# STM32_MCU.net
KiCad netlist of a schematic drawn in Altium Designer
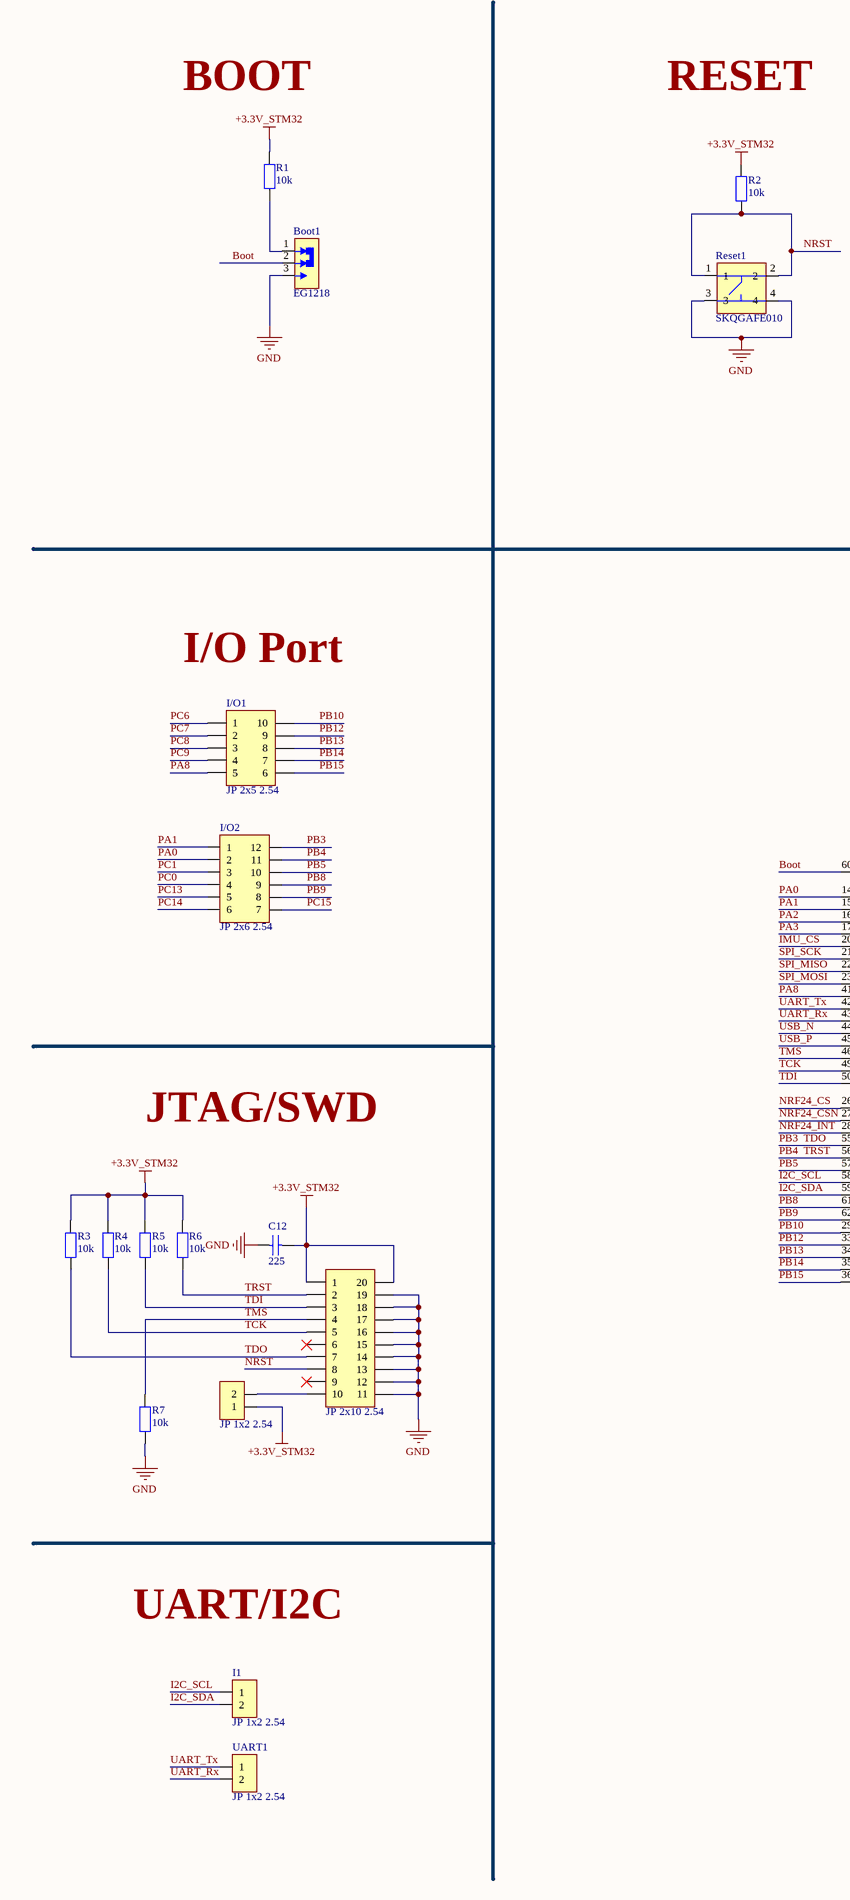
[diagram p0: STM32_MCU.SchDoc, left]
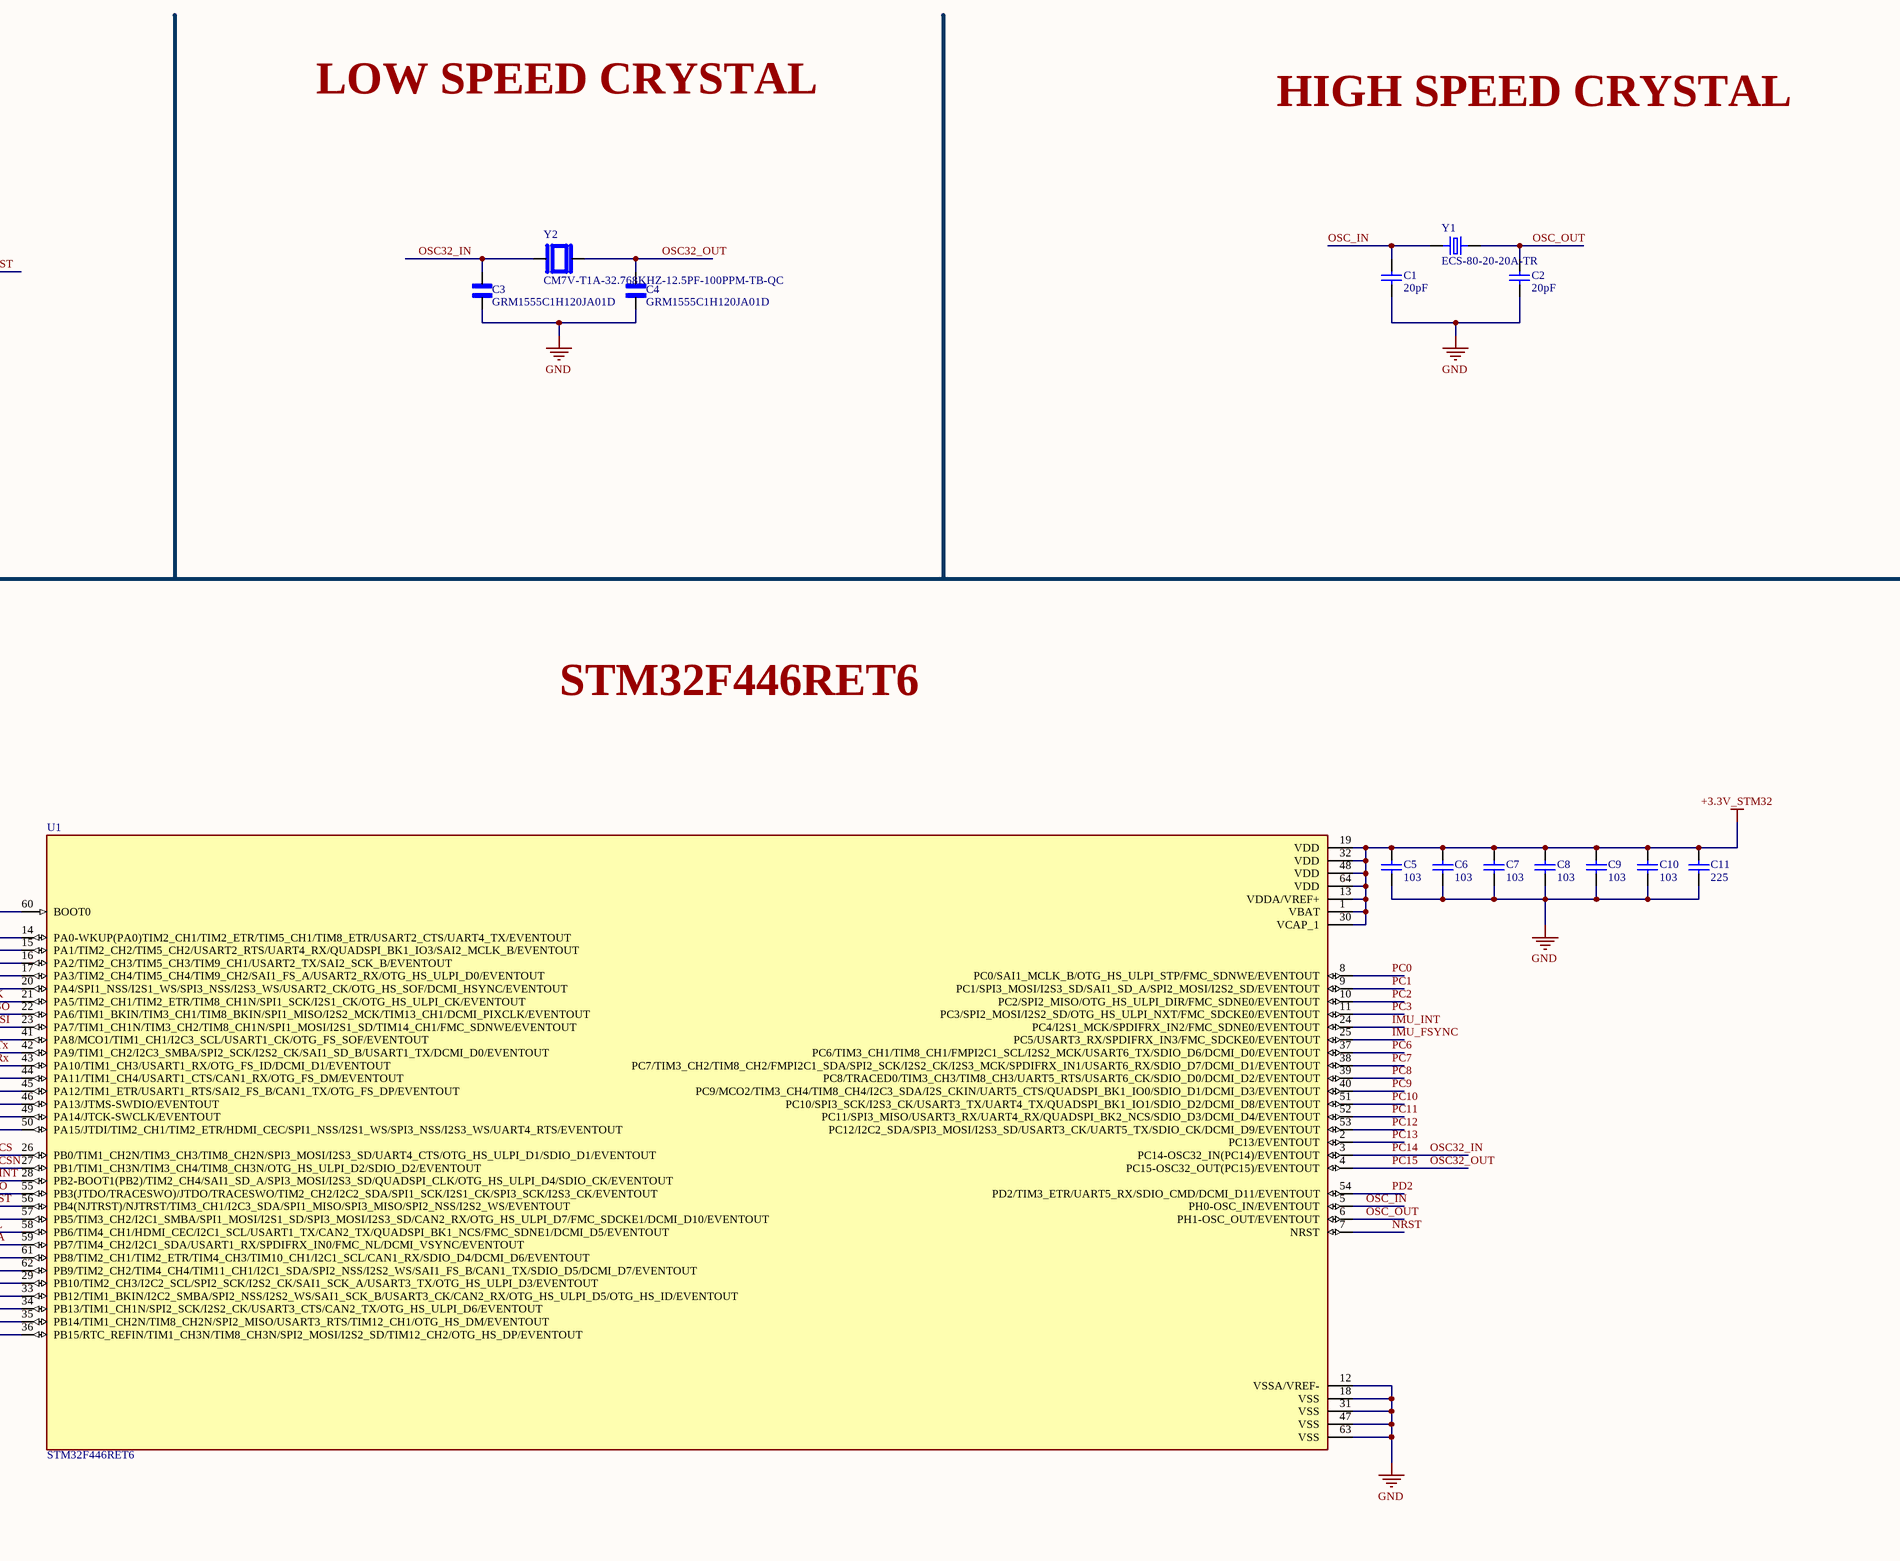
[diagram p1: STM32_MCU.SchDoc, right]

(export (version "E")
  (design (tool "Eeschema 10.0.6"))
  (components
    (comp (ref "Boot1")
      (value "EG1218")
      (footprint "SW_EG1218")
      (description "Slide Switch, EG Series, SPDT, Non-Shorting, ON-ON, 200mA DC, 30VDC, PC Pin ¦ E-Switch EG1218")
      (fields (field (name "MF") "E-Switch"))
      (libsource (lib "EG1218") (part "EG1218"))
    )
    (comp (ref "C1")
      (value "20pF")
      (footprint "tu 0805")
      (description "Dán")
      (libsource (lib "Altium_Lib_by_KhueNguyenCreator") (part "Tu 0805 20pF 50V 10%"))
    )
    (comp (ref "C2")
      (value "20pF")
      (footprint "tu 0805")
      (description "Dán")
      (libsource (lib "Altium_Lib_by_KhueNguyenCreator") (part "Tu 0805 20pF 50V 10%"))
    )
    (comp (ref "C3")
      (value "GRM1555C1H120JA01D")
      (footprint "GRM1555C1H120JA01D:CAPC1005X55N")
      (description "0402 12 pF 50 V Â±5% Tolerance C0G SMT Multilayer Ceramic Capacitor")
      (fields (field (name "MF") "{'manufacturer': u'Murata'}"))
      (libsource (lib "*") (part "GRM1555C1H120JA01D"))
    )
    (comp (ref "C4")
      (value "GRM1555C1H120JA01D")
      (footprint "GRM1555C1H120JA01D:CAPC1005X55N")
      (description "0402 12 pF 50 V Â±5% Tolerance C0G SMT Multilayer Ceramic Capacitor")
      (fields (field (name "MF") "{'manufacturer': u'Murata'}"))
      (libsource (lib "*") (part "GRM1555C1H120JA01D"))
    )
    (comp (ref "C5")
      (value "103")
      (footprint "tu 0603")
      (description "Dán")
      (libsource (lib "Altium_Lib_by_KhueNguyenCreator") (part "Tu 0603 103 50V 10%"))
    )
    (comp (ref "C6")
      (value "103")
      (footprint "tu 0603")
      (description "Dán")
      (libsource (lib "Altium_Lib_by_KhueNguyenCreator") (part "Tu 0603 103 50V 10%"))
    )
    (comp (ref "C7")
      (value "103")
      (footprint "tu 0603")
      (description "Dán")
      (libsource (lib "Altium_Lib_by_KhueNguyenCreator") (part "Tu 0603 103 50V 10%"))
    )
    (comp (ref "C8")
      (value "103")
      (footprint "tu 0603")
      (description "Dán")
      (libsource (lib "Altium_Lib_by_KhueNguyenCreator") (part "Tu 0603 103 50V 10%"))
    )
    (comp (ref "C9")
      (value "103")
      (footprint "tu 0603")
      (description "Dán")
      (libsource (lib "Altium_Lib_by_KhueNguyenCreator") (part "Tu 0603 103 50V 10%"))
    )
    (comp (ref "C10")
      (value "103")
      (footprint "tu 0603")
      (description "Dán")
      (libsource (lib "Altium_Lib_by_KhueNguyenCreator") (part "Tu 0603 103 50V 10%"))
    )
    (comp (ref "C11")
      (value "225")
      (footprint "tu 0805")
      (description "Dán")
      (libsource (lib "Altium_Lib_by_KhueNguyenCreator") (part "Tu 0805 225 25V 10%"))
    )
    (comp (ref "C12")
      (value "225")
      (footprint "tu 0805")
      (description "Dán")
      (libsource (lib "Altium_Lib_by_KhueNguyenCreator") (part "Tu 0805 225 25V 10%"))
    )
    (comp (ref "I/O1")
      (value "JP 2x5 2.54")
      (footprint "JP 2x5 DT")
      (description "Cắm")
      (libsource (lib "Altium_Lib_by_KhueNguyenCreator") (part "JP 2x5 2.54 Duc Thang"))
    )
    (comp (ref "I/O2")
      (value "JP 2x6 2.54")
      (footprint "JP 2x6 DT")
      (description "Cắm")
      (libsource (lib "Altium_Lib_by_KhueNguyenCreator") (part "JP 2x6 2.54 Duc Thang"))
    )
    (comp (ref "I1")
      (value "JP 1x2 2.54")
      (footprint "JP 1x2 DT")
      (description "Cắm")
      (libsource (lib "Altium_Lib_by_KhueNguyenCreator") (part "JP 1x2 2.54 Duc Thang"))
    )
    (comp (ref "JP1")
      (value "JP 1x2 2.54")
      (footprint "JP 1x2 DT")
      (description "Cắm")
      (libsource (lib "") (part "JP 1x2 2.54 Duc Thang_1"))
    )
    (comp (ref "R1")
      (value "10k")
      (footprint "tro smd 0603")
      (description "Dán")
      (libsource (lib "Altium_Lib_by_KhueNguyenCreator") (part "Tro 0603 1% 10k"))
    )
    (comp (ref "R2")
      (value "10k")
      (footprint "tro smd 0603")
      (description "Dán")
      (libsource (lib "Altium_Lib_by_KhueNguyenCreator") (part "Tro 0603 1% 10k"))
    )
    (comp (ref "R3")
      (value "10k")
      (footprint "tro smd 0603")
      (description "Dán")
      (libsource (lib "Altium_Lib_by_KhueNguyenCreator") (part "Tro 0603 1% 10k"))
    )
    (comp (ref "R4")
      (value "10k")
      (footprint "tro smd 0603")
      (description "Dán")
      (libsource (lib "Altium_Lib_by_KhueNguyenCreator") (part "Tro 0603 1% 10k"))
    )
    (comp (ref "R5")
      (value "10k")
      (footprint "tro smd 0603")
      (description "Dán")
      (libsource (lib "Altium_Lib_by_KhueNguyenCreator") (part "Tro 0603 1% 10k"))
    )
    (comp (ref "R6")
      (value "10k")
      (footprint "tro smd 0603")
      (description "Dán")
      (libsource (lib "Altium_Lib_by_KhueNguyenCreator") (part "Tro 0603 1% 10k"))
    )
    (comp (ref "R7")
      (value "10k")
      (footprint "tro smd 0603")
      (description "Dán")
      (libsource (lib "Altium_Lib_by_KhueNguyenCreator") (part "Tro 0603 1% 10k"))
    )
    (comp (ref "Reset1")
      (value "SKQGAFE010")
      (footprint "SW_SKQGAFE010")
      (description "Switch Tactile N.O. SPST Button Gull Wing 0.05A 12VDC 0.98N SMD T/R")
      (fields (field (name "MF") "{'manufacturer': u'ALPS'}"))
      (libsource (lib "SnapEDA_Library") (part "SKQGAFE010"))
    )
    (comp (ref "SWD/JTAG1")
      (value "JP 2x10 2.54")
      (footprint "JP 2x10 DT")
      (description "Cắm")
      (libsource (lib "Altium_Lib_by_KhueNguyenCreator") (part "JP 2x10 2.54 Duc Thang"))
    )
    (comp (ref "U1")
      (value "STM32F446RET6")
      (footprint "QFP50P1200X1200X160-64N")
      (description "MCU 32-Bit STM32 ARM Cortex M4 RISC 512KB Flash 2.5V/3.3V 64-Pin LQFP Tray")
      (fields (field (name "MF") "{'manufacturer': u'STMicroelectronics'}"))
      (libsource (lib "SnapEDA_Library") (part "STM32F446RET6"))
    )
    (comp (ref "UART1")
      (value "JP 1x2 2.54")
      (footprint "JP 1x2 DT")
      (description "Cắm")
      (libsource (lib "Altium_Lib_by_KhueNguyenCreator") (part "JP 1x2 2.54 Duc Thang"))
    )
    (comp (ref "Y1")
      (value "ECS-80-20-20A-TR")
      (footprint "ECS-80-20-20A-TR:XTAL_ECS-80-20-20A-TR")
      (description "SMD CRYSTAL")
      (fields (field (name "MF") "{'manufacturer': u'ECS Inc.'}"))
      (libsource (lib "*") (part "ECS-80-20-20A-TR"))
    )
    (comp (ref "Y2")
      (value "CM7V-T1A-32.768KHZ-12.5PF-100PPM-TB-QC")
      (footprint "XTAL_CM7V-T1A-32.768KHZ-12.5PF-100PPM-TB-QC")
      (fields (field (name "MF") "{'manufacturer': u'Micro Crystal'}"))
      (libsource (lib "SnapEDA_Library") (part "CM7V-T1A-32.768KHZ-12.5PF-100PPM-TB-QC"))
    )
  )
  (nets
    (net (code "1") (name "+3.3V_STM32") (class "Default")
      (node (ref "C10") (pin "1") (pinfunction "1_1") (pintype "passive"))
      (node (ref "C11") (pin "1") (pinfunction "1_1") (pintype "passive"))
      (node (ref "C12") (pin "1") (pinfunction "1_1") (pintype "passive"))
      (node (ref "C5") (pin "1") (pinfunction "1_1") (pintype "passive"))
      (node (ref "C6") (pin "1") (pinfunction "1_1") (pintype "passive"))
      (node (ref "C7") (pin "1") (pinfunction "1_1") (pintype "passive"))
      (node (ref "C8") (pin "1") (pinfunction "1_1") (pintype "passive"))
      (node (ref "C9") (pin "1") (pinfunction "1_1") (pintype "passive"))
      (node (ref "JP1") (pin "1") (pinfunction "1_1") (pintype "passive"))
      (node (ref "R1") (pin "2") (pinfunction "2_2") (pintype "passive"))
      (node (ref "R2") (pin "2") (pinfunction "2_2") (pintype "passive"))
      (node (ref "R3") (pin "2") (pinfunction "2_2") (pintype "passive"))
      (node (ref "R4") (pin "2") (pinfunction "2_2") (pintype "passive"))
      (node (ref "R5") (pin "2") (pinfunction "2_2") (pintype "passive"))
      (node (ref "R6") (pin "2") (pinfunction "2_2") (pintype "passive"))
      (node (ref "SWD/JTAG1") (pin "1") (pinfunction "1_1") (pintype "passive"))
      (node (ref "SWD/JTAG1") (pin "20") (pinfunction "20_20") (pintype "passive"))
      (node (ref "U1") (pin "1") (pinfunction "VBAT_1") (pintype "power_in"))
      (node (ref "U1") (pin "13") (pinfunction "VDDA/VREF+_13") (pintype "power_in"))
      (node (ref "U1") (pin "19") (pinfunction "VDD_19") (pintype "power_in"))
      (node (ref "U1") (pin "30") (pinfunction "VCAP_1_30") (pintype "power_in"))
      (node (ref "U1") (pin "32") (pinfunction "VDD_32") (pintype "power_in"))
      (node (ref "U1") (pin "48") (pinfunction "VDD_48") (pintype "power_in"))
      (node (ref "U1") (pin "64") (pinfunction "VDD_64") (pintype "power_in"))
    )
    (net (code "2") (name "/Boot") (class "Default")
      (node (ref "Boot1") (pin "2") (pinfunction "COM_2") (pintype "passive"))
      (node (ref "U1") (pin "60") (pinfunction "BOOT0_60") (pintype "input"))
    )
    (net (code "3") (name "/I2C_SCL") (class "Default")
      (node (ref "I1") (pin "1") (pinfunction "1_1") (pintype "passive"))
      (node (ref "U1") (pin "58") (pinfunction "PB6/TIM4_CH1/HDMI_CEC/I2C1_SCL/USART1_TX/CAN2_TX/QUADSPI_BK1_NCS/FMC_SDNE1/DCMI_D5/EVENTOUT_58") (pintype "bidirectional"))
    )
    (net (code "4") (name "/I2C_SDA") (class "Default")
      (node (ref "I1") (pin "2") (pinfunction "2_2") (pintype "passive"))
      (node (ref "U1") (pin "59") (pinfunction "PB7/TIM4_CH2/I2C1_SDA/USART1_RX/SPDIFRX_IN0/FMC_NL/DCMI_VSYNC/EVENTOUT_59") (pintype "bidirectional"))
    )
    (net (code "5") (name "/IMU_CS") (class "Default")
      (node (ref "U1") (pin "20") (pinfunction "PA4/SPI1_NSS/I2S1_WS/SPI3_NSS/I2S3_WS/USART2_CK/OTG_HS_SOF/DCMI_HSYNC/EVENTOUT_20") (pintype "bidirectional"))
    )
    (net (code "6") (name "/IMU_FSYNC") (class "Default")
      (node (ref "U1") (pin "25") (pinfunction "PC5/USART3_RX/SPDIFRX_IN3/FMC_SDCKE0/EVENTOUT_25") (pintype "bidirectional"))
    )
    (net (code "7") (name "/IMU_INT") (class "Default")
      (node (ref "U1") (pin "24") (pinfunction "PC4/I2S1_MCK/SPDIFRX_IN2/FMC_SDNE0/EVENTOUT_24") (pintype "bidirectional"))
    )
    (net (code "8") (name "/NRF24_CS") (class "Default")
      (node (ref "U1") (pin "26") (pinfunction "PB0/TIM1_CH2N/TIM3_CH3/TIM8_CH2N/SPI3_MOSI/I2S3_SD/UART4_CTS/OTG_HS_ULPI_D1/SDIO_D1/EVENTOUT_26") (pintype "bidirectional"))
    )
    (net (code "9") (name "/NRF24_CSN") (class "Default")
      (node (ref "U1") (pin "27") (pinfunction "PB1/TIM1_CH3N/TIM3_CH4/TIM8_CH3N/OTG_HS_ULPI_D2/SDIO_D2/EVENTOUT_27") (pintype "bidirectional"))
    )
    (net (code "10") (name "/NRF24_INT") (class "Default")
      (node (ref "U1") (pin "28") (pinfunction "PB2-BOOT1(PB2)/TIM2_CH4/SAI1_SD_A/SPI3_MOSI/I2S3_SD/QUADSPI_CLK/OTG_HS_ULPI_D4/SDIO_CK/EVENTOUT_28") (pintype "bidirectional"))
    )
    (net (code "11") (name "/NRST") (class "Default")
      (node (ref "R2") (pin "1") (pinfunction "1_1") (pintype "passive"))
      (node (ref "Reset1") (pin "1") (pinfunction "1_1") (pintype "passive"))
      (node (ref "Reset1") (pin "2") (pinfunction "2_2") (pintype "passive"))
      (node (ref "SWD/JTAG1") (pin "8") (pinfunction "8_8") (pintype "passive"))
      (node (ref "U1") (pin "7") (pinfunction "NRST_7") (pintype "bidirectional"))
    )
    (net (code "12") (name "/OSC32_IN") (class "Default")
      (node (ref "C3") (pin "2") (pinfunction "2_2") (pintype "passive"))
      (node (ref "I/O2") (pin "6") (pinfunction "6_6") (pintype "passive"))
      (node (ref "U1") (pin "3") (pinfunction "PC14-OSC32_IN(PC14)/EVENTOUT_3") (pintype "bidirectional"))
      (node (ref "Y2") (pin "1") (pinfunction "1_1") (pintype "passive"))
    )
    (net (code "13") (name "/OSC32_OUT") (class "Default")
      (node (ref "C4") (pin "2") (pinfunction "2_2") (pintype "passive"))
      (node (ref "I/O2") (pin "7") (pinfunction "7_7") (pintype "passive"))
      (node (ref "U1") (pin "4") (pinfunction "PC15-OSC32_OUT(PC15)/EVENTOUT_4") (pintype "bidirectional"))
      (node (ref "Y2") (pin "2") (pinfunction "2_2") (pintype "passive"))
    )
    (net (code "14") (name "/OSC_IN") (class "Default")
      (node (ref "C1") (pin "1") (pinfunction "1_1") (pintype "passive"))
      (node (ref "U1") (pin "5") (pinfunction "PH0-OSC_IN/EVENTOUT_5") (pintype "bidirectional"))
      (node (ref "Y1") (pin "1") (pinfunction "1_1") (pintype "passive"))
    )
    (net (code "15") (name "/OSC_OUT") (class "Default")
      (node (ref "C2") (pin "1") (pinfunction "1_1") (pintype "passive"))
      (node (ref "U1") (pin "6") (pinfunction "PH1-OSC_OUT/EVENTOUT_6") (pintype "bidirectional"))
      (node (ref "Y1") (pin "2") (pinfunction "2_2") (pintype "passive"))
    )
    (net (code "16") (name "/PA0") (class "Default")
      (node (ref "I/O2") (pin "2") (pinfunction "2_2") (pintype "passive"))
      (node (ref "U1") (pin "14") (pinfunction "PA0-WKUP(PA0)TIM2_CH1/TIM2_ETR/TIM5_CH1/TIM8_ETR/USART2_CTS/UART4_TX/EVENTOUT_14") (pintype "bidirectional"))
    )
    (net (code "17") (name "/PA1") (class "Default")
      (node (ref "I/O2") (pin "1") (pinfunction "1_1") (pintype "passive"))
      (node (ref "U1") (pin "15") (pinfunction "PA1/TIM2_CH2/TIM5_CH2/USART2_RTS/UART4_RX/QUADSPI_BK1_IO3/SAI2_MCLK_B/EVENTOUT_15") (pintype "bidirectional"))
    )
    (net (code "18") (name "/PA2") (class "Default")
      (node (ref "U1") (pin "16") (pinfunction "PA2/TIM2_CH3/TIM5_CH3/TIM9_CH1/USART2_TX/SAI2_SCK_B/EVENTOUT_16") (pintype "bidirectional"))
    )
    (net (code "19") (name "/PA3") (class "Default")
      (node (ref "U1") (pin "17") (pinfunction "PA3/TIM2_CH4/TIM5_CH4/TIM9_CH2/SAI1_FS_A/USART2_RX/OTG_HS_ULPI_D0/EVENTOUT_17") (pintype "bidirectional"))
    )
    (net (code "20") (name "/PA8") (class "Default")
      (node (ref "I/O1") (pin "5") (pinfunction "5_5") (pintype "passive"))
      (node (ref "U1") (pin "41") (pinfunction "PA8/MCO1/TIM1_CH1/I2C3_SCL/USART1_CK/OTG_FS_SOF/EVENTOUT_41") (pintype "bidirectional"))
    )
    (net (code "21") (name "/PB3") (class "Default")
      (node (ref "I/O2") (pin "12") (pinfunction "12_12") (pintype "passive"))
      (node (ref "R3") (pin "1") (pinfunction "1_1") (pintype "passive"))
      (node (ref "SWD/JTAG1") (pin "7") (pinfunction "7_7") (pintype "passive"))
      (node (ref "U1") (pin "55") (pinfunction "PB3(JTDO/TRACESWO)/JTDO/TRACESWO/TIM2_CH2/I2C2_SDA/SPI1_SCK/I2S1_CK/SPI3_SCK/I2S3_CK/EVENTOUT_55") (pintype "bidirectional"))
    )
    (net (code "22") (name "/PB4") (class "Default")
      (node (ref "I/O2") (pin "11") (pinfunction "11_11") (pintype "passive"))
      (node (ref "R6") (pin "1") (pinfunction "1_1") (pintype "passive"))
      (node (ref "SWD/JTAG1") (pin "2") (pinfunction "2_2") (pintype "passive"))
      (node (ref "U1") (pin "56") (pinfunction "PB4(NJTRST)/NJTRST/TIM3_CH1/I2C3_SDA/SPI1_MISO/SPI3_MISO/SPI2_NSS/I2S2_WS/EVENTOUT_56") (pintype "bidirectional"))
    )
    (net (code "23") (name "/PB5") (class "Default")
      (node (ref "I/O2") (pin "10") (pinfunction "10_10") (pintype "passive"))
      (node (ref "U1") (pin "57") (pinfunction "PB5/TIM3_CH2/I2C1_SMBA/SPI1_MOSI/I2S1_SD/SPI3_MOSI/I2S3_SD/CAN2_RX/OTG_HS_ULPI_D7/FMC_SDCKE1/DCMI_D10/EVENTOUT_57") (pintype "bidirectional"))
    )
    (net (code "24") (name "/PB8") (class "Default")
      (node (ref "I/O2") (pin "9") (pinfunction "9_9") (pintype "passive"))
      (node (ref "U1") (pin "61") (pinfunction "PB8/TIM2_CH1/TIM2_ETR/TIM4_CH3/TIM10_CH1/I2C1_SCL/CAN1_RX/SDIO_D4/DCMI_D6/EVENTOUT_61") (pintype "bidirectional"))
    )
    (net (code "25") (name "/PB9") (class "Default")
      (node (ref "I/O2") (pin "8") (pinfunction "8_8") (pintype "passive"))
      (node (ref "U1") (pin "62") (pinfunction "PB9/TIM2_CH2/TIM4_CH4/TIM11_CH1/I2C1_SDA/SPI2_NSS/I2S2_WS/SAI1_FS_B/CAN1_TX/SDIO_D5/DCMI_D7/EVENTOUT_62") (pintype "bidirectional"))
    )
    (net (code "26") (name "/PB10") (class "Default")
      (node (ref "I/O1") (pin "10") (pinfunction "10_10") (pintype "passive"))
      (node (ref "U1") (pin "29") (pinfunction "PB10/TIM2_CH3/I2C2_SCL/SPI2_SCK/I2S2_CK/SAI1_SCK_A/USART3_TX/OTG_HS_ULPI_D3/EVENTOUT_29") (pintype "bidirectional"))
    )
    (net (code "27") (name "/PB12") (class "Default")
      (node (ref "I/O1") (pin "9") (pinfunction "9_9") (pintype "passive"))
      (node (ref "U1") (pin "33") (pinfunction "PB12/TIM1_BKIN/I2C2_SMBA/SPI2_NSS/I2S2_WS/SAI1_SCK_B/USART3_CK/CAN2_RX/OTG_HS_ULPI_D5/OTG_HS_ID/EVENTOUT_33") (pintype "bidirectional"))
    )
    (net (code "28") (name "/PB13") (class "Default")
      (node (ref "I/O1") (pin "8") (pinfunction "8_8") (pintype "passive"))
      (node (ref "U1") (pin "34") (pinfunction "PB13/TIM1_CH1N/SPI2_SCK/I2S2_CK/USART3_CTS/CAN2_TX/OTG_HS_ULPI_D6/EVENTOUT_34") (pintype "bidirectional"))
    )
    (net (code "29") (name "/PB14") (class "Default")
      (node (ref "I/O1") (pin "7") (pinfunction "7_7") (pintype "passive"))
      (node (ref "U1") (pin "35") (pinfunction "PB14/TIM1_CH2N/TIM8_CH2N/SPI2_MISO/USART3_RTS/TIM12_CH1/OTG_HS_DM/EVENTOUT_35") (pintype "bidirectional"))
    )
    (net (code "30") (name "/PB15") (class "Default")
      (node (ref "I/O1") (pin "6") (pinfunction "6_6") (pintype "passive"))
      (node (ref "U1") (pin "36") (pinfunction "PB15/RTC_REFIN/TIM1_CH3N/TIM8_CH3N/SPI2_MOSI/I2S2_SD/TIM12_CH2/OTG_HS_DP/EVENTOUT_36") (pintype "bidirectional"))
    )
    (net (code "31") (name "/PC0") (class "Default")
      (node (ref "I/O2") (pin "4") (pinfunction "4_4") (pintype "passive"))
      (node (ref "U1") (pin "8") (pinfunction "PC0/SAI1_MCLK_B/OTG_HS_ULPI_STP/FMC_SDNWE/EVENTOUT_8") (pintype "bidirectional"))
    )
    (net (code "32") (name "/PC1") (class "Default")
      (node (ref "I/O2") (pin "3") (pinfunction "3_3") (pintype "passive"))
      (node (ref "U1") (pin "9") (pinfunction "PC1/SPI3_MOSI/I2S3_SD/SAI1_SD_A/SPI2_MOSI/I2S2_SD/EVENTOUT_9") (pintype "bidirectional"))
    )
    (net (code "33") (name "/PC2") (class "Default")
      (node (ref "U1") (pin "10") (pinfunction "PC2/SPI2_MISO/OTG_HS_ULPI_DIR/FMC_SDNE0/EVENTOUT_10") (pintype "bidirectional"))
    )
    (net (code "34") (name "/PC3") (class "Default")
      (node (ref "U1") (pin "11") (pinfunction "PC3/SPI2_MOSI/I2S2_SD/OTG_HS_ULPI_NXT/FMC_SDCKE0/EVENTOUT_11") (pintype "bidirectional"))
    )
    (net (code "35") (name "/PC6") (class "Default")
      (node (ref "I/O1") (pin "1") (pinfunction "1_1") (pintype "passive"))
      (node (ref "U1") (pin "37") (pinfunction "PC6/TIM3_CH1/TIM8_CH1/FMPI2C1_SCL/I2S2_MCK/USART6_TX/SDIO_D6/DCMI_D0/EVENTOUT_37") (pintype "bidirectional"))
    )
    (net (code "36") (name "/PC7") (class "Default")
      (node (ref "I/O1") (pin "2") (pinfunction "2_2") (pintype "passive"))
      (node (ref "U1") (pin "38") (pinfunction "PC7/TIM3_CH2/TIM8_CH2/FMPI2C1_SDA/SPI2_SCK/I2S2_CK/I2S3_MCK/SPDIFRX_IN1/USART6_RX/SDIO_D7/DCMI_D1/EVENTOUT_38") (pintype "bidirectional"))
    )
    (net (code "37") (name "/PC8") (class "Default")
      (node (ref "I/O1") (pin "3") (pinfunction "3_3") (pintype "passive"))
      (node (ref "U1") (pin "39") (pinfunction "PC8/TRACED0/TIM3_CH3/TIM8_CH3/UART5_RTS/USART6_CK/SDIO_D0/DCMI_D2/EVENTOUT_39") (pintype "bidirectional"))
    )
    (net (code "38") (name "/PC9") (class "Default")
      (node (ref "I/O1") (pin "4") (pinfunction "4_4") (pintype "passive"))
      (node (ref "U1") (pin "40") (pinfunction "PC9/MCO2/TIM3_CH4/TIM8_CH4/I2C3_SDA/I2S_CKIN/UART5_CTS/QUADSPI_BK1_IO0/SDIO_D1/DCMI_D3/EVENTOUT_40") (pintype "bidirectional"))
    )
    (net (code "39") (name "/PC10") (class "Default")
      (node (ref "U1") (pin "51") (pinfunction "PC10/SPI3_SCK/I2S3_CK/USART3_TX/UART4_TX/QUADSPI_BK1_IO1/SDIO_D2/DCMI_D8/EVENTOUT_51") (pintype "bidirectional"))
    )
    (net (code "40") (name "/PC11") (class "Default")
      (node (ref "U1") (pin "52") (pinfunction "PC11/SPI3_MISO/USART3_RX/UART4_RX/QUADSPI_BK2_NCS/SDIO_D3/DCMI_D4/EVENTOUT_52") (pintype "bidirectional"))
    )
    (net (code "41") (name "/PC12") (class "Default")
      (node (ref "U1") (pin "53") (pinfunction "PC12/I2C2_SDA/SPI3_MOSI/I2S3_SD/USART3_CK/UART5_TX/SDIO_CK/DCMI_D9/EVENTOUT_53") (pintype "bidirectional"))
    )
    (net (code "42") (name "/PC13") (class "Default")
      (node (ref "I/O2") (pin "5") (pinfunction "5_5") (pintype "passive"))
      (node (ref "U1") (pin "2") (pinfunction "PC13/EVENTOUT_2") (pintype "bidirectional"))
    )
    (net (code "43") (name "/PD2") (class "Default")
      (node (ref "U1") (pin "54") (pinfunction "PD2/TIM3_ETR/UART5_RX/SDIO_CMD/DCMI_D11/EVENTOUT_54") (pintype "bidirectional"))
    )
    (net (code "44") (name "/SPI_MISO") (class "Default")
      (node (ref "U1") (pin "22") (pinfunction "PA6/TIM1_BKIN/TIM3_CH1/TIM8_BKIN/SPI1_MISO/I2S2_MCK/TIM13_CH1/DCMI_PIXCLK/EVENTOUT_22") (pintype "bidirectional"))
    )
    (net (code "45") (name "/SPI_MOSI") (class "Default")
      (node (ref "U1") (pin "23") (pinfunction "PA7/TIM1_CH1N/TIM3_CH2/TIM8_CH1N/SPI1_MOSI/I2S1_SD/TIM14_CH1/FMC_SDNWE/EVENTOUT_23") (pintype "bidirectional"))
    )
    (net (code "46") (name "/SPI_SCK") (class "Default")
      (node (ref "U1") (pin "21") (pinfunction "PA5/TIM2_CH1/TIM2_ETR/TIM8_CH1N/SPI1_SCK/I2S1_CK/OTG_HS_ULPI_CK/EVENTOUT_21") (pintype "bidirectional"))
    )
    (net (code "47") (name "/TCK") (class "Default")
      (node (ref "R4") (pin "1") (pinfunction "1_1") (pintype "passive"))
      (node (ref "SWD/JTAG1") (pin "5") (pinfunction "5_5") (pintype "passive"))
      (node (ref "U1") (pin "49") (pinfunction "PA14/JTCK-SWCLK/EVENTOUT_49") (pintype "bidirectional"))
    )
    (net (code "48") (name "/TDI") (class "Default")
      (node (ref "R5") (pin "1") (pinfunction "1_1") (pintype "passive"))
      (node (ref "SWD/JTAG1") (pin "3") (pinfunction "3_3") (pintype "passive"))
      (node (ref "U1") (pin "50") (pinfunction "PA15/JTDI/TIM2_CH1/TIM2_ETR/HDMI_CEC/SPI1_NSS/I2S1_WS/SPI3_NSS/I2S3_WS/UART4_RTS/EVENTOUT_50") (pintype "bidirectional"))
    )
    (net (code "49") (name "/TMS") (class "Default")
      (node (ref "R7") (pin "2") (pinfunction "2_2") (pintype "passive"))
      (node (ref "SWD/JTAG1") (pin "4") (pinfunction "4_4") (pintype "passive"))
      (node (ref "U1") (pin "46") (pinfunction "PA13/JTMS-SWDIO/EVENTOUT_46") (pintype "bidirectional"))
    )
    (net (code "50") (name "/UART_Rx") (class "Default")
      (node (ref "U1") (pin "43") (pinfunction "PA10/TIM1_CH3/USART1_RX/OTG_FS_ID/DCMI_D1/EVENTOUT_43") (pintype "bidirectional"))
      (node (ref "UART1") (pin "2") (pinfunction "2_2") (pintype "passive"))
    )
    (net (code "51") (name "/UART_Tx") (class "Default")
      (node (ref "U1") (pin "42") (pinfunction "PA9/TIM1_CH2/I2C3_SMBA/SPI2_SCK/I2S2_CK/SAI1_SD_B/USART1_TX/DCMI_D0/EVENTOUT_42") (pintype "bidirectional"))
      (node (ref "UART1") (pin "1") (pinfunction "1_1") (pintype "passive"))
    )
    (net (code "52") (name "/USB_N") (class "Default")
      (node (ref "U1") (pin "44") (pinfunction "PA11/TIM1_CH4/USART1_CTS/CAN1_RX/OTG_FS_DM/EVENTOUT_44") (pintype "bidirectional"))
    )
    (net (code "53") (name "/USB_P") (class "Default")
      (node (ref "U1") (pin "45") (pinfunction "PA12/TIM1_ETR/USART1_RTS/SAI2_FS_B/CAN1_TX/OTG_FS_DP/EVENTOUT_45") (pintype "bidirectional"))
    )
    (net (code "54") (name "GND") (class "Default")
      (node (ref "Boot1") (pin "3") (pinfunction "NO_3") (pintype "passive"))
      (node (ref "C1") (pin "2") (pinfunction "2_2") (pintype "passive"))
      (node (ref "C10") (pin "2") (pinfunction "2_2") (pintype "passive"))
      (node (ref "C11") (pin "2") (pinfunction "2_2") (pintype "passive"))
      (node (ref "C12") (pin "2") (pinfunction "2_2") (pintype "passive"))
      (node (ref "C2") (pin "2") (pinfunction "2_2") (pintype "passive"))
      (node (ref "C3") (pin "1") (pinfunction "1_1") (pintype "passive"))
      (node (ref "C4") (pin "1") (pinfunction "1_1") (pintype "passive"))
      (node (ref "C5") (pin "2") (pinfunction "2_2") (pintype "passive"))
      (node (ref "C6") (pin "2") (pinfunction "2_2") (pintype "passive"))
      (node (ref "C7") (pin "2") (pinfunction "2_2") (pintype "passive"))
      (node (ref "C8") (pin "2") (pinfunction "2_2") (pintype "passive"))
      (node (ref "C9") (pin "2") (pinfunction "2_2") (pintype "passive"))
      (node (ref "R7") (pin "1") (pinfunction "1_1") (pintype "passive"))
      (node (ref "Reset1") (pin "3") (pinfunction "3_3") (pintype "passive"))
      (node (ref "Reset1") (pin "4") (pinfunction "4_4") (pintype "passive"))
      (node (ref "SWD/JTAG1") (pin "11") (pinfunction "11_11") (pintype "passive"))
      (node (ref "SWD/JTAG1") (pin "12") (pinfunction "12_12") (pintype "passive"))
      (node (ref "SWD/JTAG1") (pin "13") (pinfunction "13_13") (pintype "passive"))
      (node (ref "SWD/JTAG1") (pin "14") (pinfunction "14_14") (pintype "passive"))
      (node (ref "SWD/JTAG1") (pin "15") (pinfunction "15_15") (pintype "passive"))
      (node (ref "SWD/JTAG1") (pin "16") (pinfunction "16_16") (pintype "passive"))
      (node (ref "SWD/JTAG1") (pin "17") (pinfunction "17_17") (pintype "passive"))
      (node (ref "SWD/JTAG1") (pin "18") (pinfunction "18_18") (pintype "passive"))
      (node (ref "SWD/JTAG1") (pin "19") (pinfunction "19_19") (pintype "passive"))
      (node (ref "U1") (pin "12") (pinfunction "VSSA/VREF-_12") (pintype "power_in"))
      (node (ref "U1") (pin "18") (pinfunction "VSS_18") (pintype "power_in"))
      (node (ref "U1") (pin "31") (pinfunction "VSS_31") (pintype "power_in"))
      (node (ref "U1") (pin "47") (pinfunction "VSS_47") (pintype "power_in"))
      (node (ref "U1") (pin "63") (pinfunction "VSS_63") (pintype "power_in"))
    )
    (net (code "55") (name "Net-(Boot1-NC)") (class "Default")
      (node (ref "Boot1") (pin "1") (pinfunction "NC_1") (pintype "passive"))
      (node (ref "R1") (pin "1") (pinfunction "1_1") (pintype "passive"))
    )
    (net (code "56") (name "Net-(JP1-Pad2)") (class "Default")
      (node (ref "JP1") (pin "2") (pinfunction "2_2") (pintype "passive"))
      (node (ref "SWD/JTAG1") (pin "10") (pinfunction "10_10") (pintype "passive"))
    )
    (net (code "57") (name "unconnected-(SWD/JTAG1-Pad6)") (class "Default")
      (node (ref "SWD/JTAG1") (pin "6") (pinfunction "6_6") (pintype "passive+no_connect"))
    )
    (net (code "58") (name "unconnected-(SWD/JTAG1-Pad9)") (class "Default")
      (node (ref "SWD/JTAG1") (pin "9") (pinfunction "9_9") (pintype "passive+no_connect"))
    )
  )
)
